# Sensors_v2.net
KiCad netlist of a schematic drawn in EAGLE
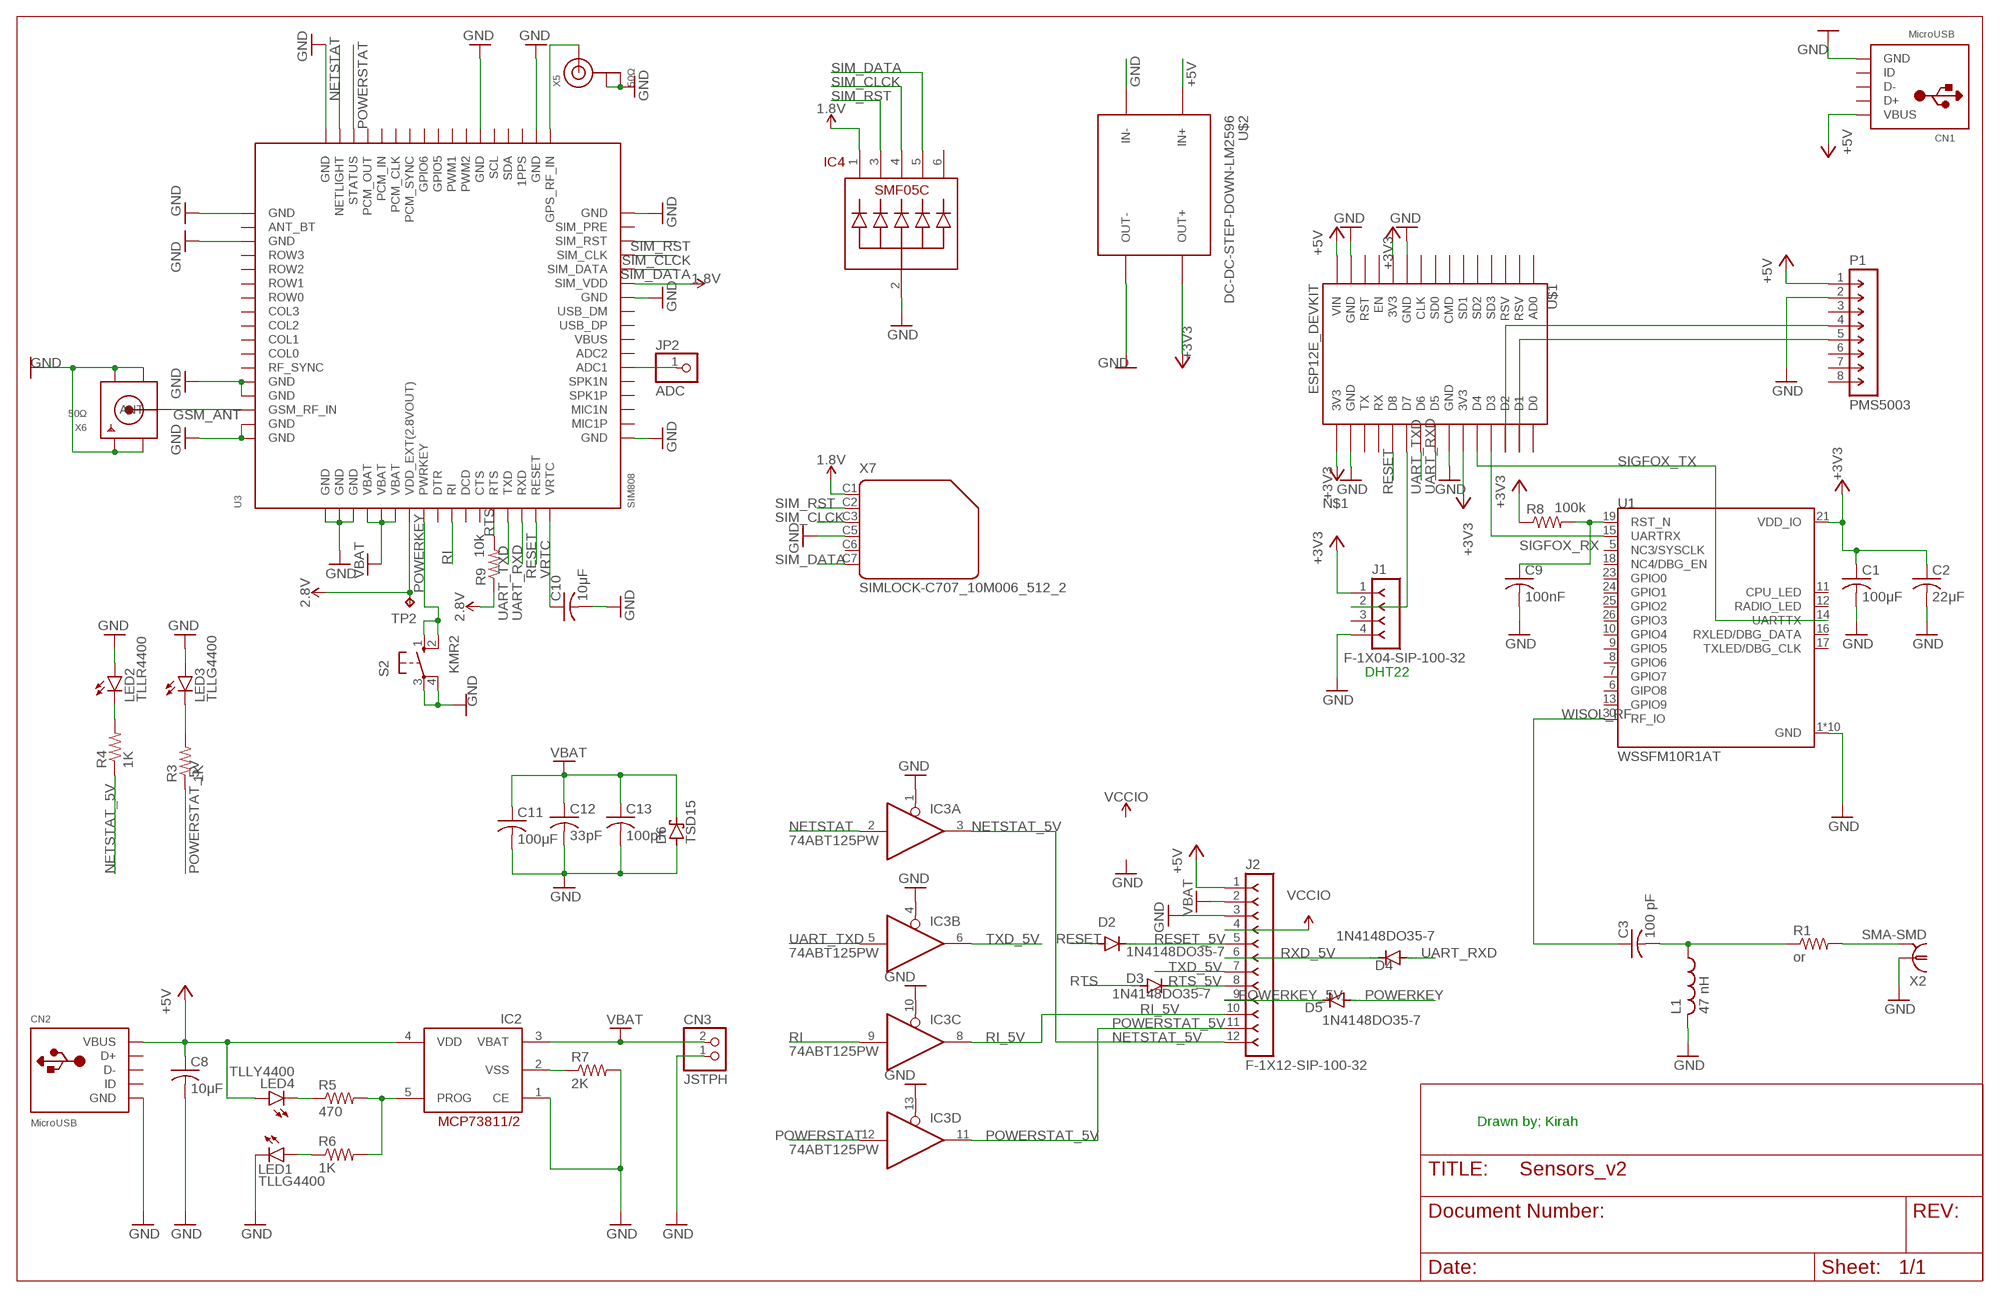
[diagram p0: schematic, sheet 1]

(export (version "E")
  (design (tool "Eeschema 10.0.6"))
  (components
    (comp (ref "C1")
      (value "100μF")
      (footprint "eagle-import:C0201")
      (libsource (lib "eagle-import") (part "C-USC0201"))
    )
    (comp (ref "C2")
      (value "22μF")
      (footprint "eagle-import:C0201")
      (libsource (lib "eagle-import") (part "C-USC0201"))
    )
    (comp (ref "C3")
      (value "100 pF")
      (footprint "eagle-import:C0201")
      (libsource (lib "eagle-import") (part "C-USC0201"))
    )
    (comp (ref "C8")
      (value "10μF")
      (footprint "eagle-import:C025-025X050")
      (libsource (lib "eagle-import") (part "C-US025-025X050"))
    )
    (comp (ref "C9")
      (value "100nF")
      (footprint "eagle-import:C025-025X050")
      (libsource (lib "eagle-import") (part "rcl_C-US025-025X050"))
    )
    (comp (ref "C10")
      (value "10μF")
      (footprint "eagle-import:C0402")
      (libsource (lib "eagle-import") (part "rcl_C-USC0402"))
    )
    (comp (ref "C11")
      (value "100μF")
      (footprint "eagle-import:C0402")
      (libsource (lib "eagle-import") (part "rcl_C-USC0402"))
    )
    (comp (ref "C12")
      (value "33pF")
      (footprint "eagle-import:C0402")
      (libsource (lib "eagle-import") (part "rcl_C-USC0402"))
    )
    (comp (ref "C13")
      (value "100pF")
      (footprint "eagle-import:C0402")
      (libsource (lib "eagle-import") (part "rcl_C-USC0402"))
    )
    (comp (ref "CN1")
      (value "MicroUSB")
      (footprint "eagle-import:USB-MINIB")
      (libsource (lib "eagle-import") (part "USBMINIB"))
    )
    (comp (ref "CN2")
      (value "MicroUSB")
      (footprint "eagle-import:USB-MINIB")
      (libsource (lib "eagle-import") (part "adafruit@1_USBMINIB"))
    )
    (comp (ref "CN3")
      (value "JSTPH")
      (footprint "eagle-import:JST-PH-2-SMT")
      (libsource (lib "eagle-import") (part "JST_2PIN-SMT"))
    )
    (comp (ref "D2")
      (value "1N4148DO35-7")
      (footprint "eagle-import:DO35-7")
      (libsource (lib "eagle-import") (part "1N4148DO35-7"))
    )
    (comp (ref "D3")
      (value "1N4148DO35-7")
      (footprint "eagle-import:DO35-7")
      (libsource (lib "eagle-import") (part "1N4148DO35-7"))
    )
    (comp (ref "D4")
      (value "1N4148DO35-7")
      (footprint "eagle-import:DO35-7")
      (libsource (lib "eagle-import") (part "1N4148DO35-7"))
    )
    (comp (ref "D5")
      (value "1N4148DO35-7")
      (footprint "eagle-import:DO35-7")
      (libsource (lib "eagle-import") (part "1N4148DO35-7"))
    )
    (comp (ref "D6")
      (value "TSD15")
      (footprint "eagle-import:CB429-15")
      (libsource (lib "eagle-import") (part "TSD15"))
    )
    (comp (ref "IC2")
      (value "MCP73811/2")
      (footprint "eagle-import:SOT23-5L")
      (libsource (lib "eagle-import") (part "MCP73811/2"))
    )
    (comp (ref "IC3")
      (value "74ABT125PW")
      (footprint "eagle-import:TSSOP14")
      (libsource (lib "eagle-import") (part "74125PWABT"))
    )
    (comp (ref "IC4")
      (value "SMF05C")
      (footprint "eagle-import:SC-70-6")
      (libsource (lib "eagle-import") (part "SMF05C"))
    )
    (comp (ref "J1")
      (value "F-1X04-SIP-100-32")
      (footprint "eagle-import:SIP-100-04-32")
      (libsource (lib "eagle-import") (part "F-1X04-SIP-100-32"))
    )
    (comp (ref "J2")
      (value "F-1X12-SIP-100-32")
      (footprint "eagle-import:SIP-100-12-32")
      (libsource (lib "eagle-import") (part "F-1X12-SIP-100-32"))
    )
    (comp (ref "JP2")
      (value "ADC")
      (footprint "eagle-import:1X01M")
      (libsource (lib "eagle-import") (part "PINHD-1X01_2.00"))
    )
    (comp (ref "L1")
      (value "47 nH")
      (footprint "eagle-import:0204_7")
      (libsource (lib "eagle-import") (part "L-US0204/7"))
    )
    (comp (ref "LED1")
      (value "TLLG4400")
      (footprint "eagle-import:LED3MM")
      (fields (field (name "MF") "VISHAY SEMICONDUCTOR"))
      (libsource (lib "eagle-import") (part "TLLG4400"))
    )
    (comp (ref "LED2")
      (value "TLLR4400")
      (footprint "eagle-import:LED3MM")
      (fields (field (name "MF") "VISHAY SEMICONDUCTOR"))
      (libsource (lib "eagle-import") (part "TLLR4400"))
    )
    (comp (ref "LED3")
      (value "TLLG4400")
      (footprint "eagle-import:LED3MM")
      (fields (field (name "MF") "VISHAY SEMICONDUCTOR"))
      (libsource (lib "eagle-import") (part "TLLG4400"))
    )
    (comp (ref "LED4")
      (value "TLLY4400")
      (footprint "eagle-import:LED3MM")
      (fields (field (name "MF") "VISHAY SEMICONDUCTOR"))
      (libsource (lib "eagle-import") (part "TLLY4400"))
    )
    (comp (ref "P1")
      (value "PMS5003")
      (footprint "eagle-import:SIP-100-08-40")
      (libsource (lib "eagle-import") (part "M-1X08-SIP-100-40"))
    )
    (comp (ref "R1")
      (value "or")
      (footprint "eagle-import:0204_5")
      (libsource (lib "eagle-import") (part "R-US_0204/5"))
    )
    (comp (ref "R3")
      (value "1K")
      (footprint "eagle-import:0204_5")
      (libsource (lib "eagle-import") (part "R-US_0204/5"))
    )
    (comp (ref "R4")
      (value "1K")
      (footprint "eagle-import:0204_5")
      (libsource (lib "eagle-import") (part "R-US_0204/5"))
    )
    (comp (ref "R5")
      (value "470")
      (footprint "eagle-import:0204_5")
      (libsource (lib "eagle-import") (part "R-US_0204/5"))
    )
    (comp (ref "R6")
      (value "1K")
      (footprint "eagle-import:0204_5")
      (libsource (lib "eagle-import") (part "R-US_0204/5"))
    )
    (comp (ref "R7")
      (value "2K")
      (footprint "eagle-import:0204_5")
      (libsource (lib "eagle-import") (part "R-US_0204/5"))
    )
    (comp (ref "R8")
      (value "100k")
      (footprint "eagle-import:0204_7")
      (libsource (lib "eagle-import") (part "R-US_0204/7"))
    )
    (comp (ref "R9")
      (value "10k")
      (footprint "eagle-import:0204_5")
      (libsource (lib "eagle-import") (part "R-US_0204/5"))
    )
    (comp (ref "S2")
      (value "KMR2")
      (footprint "eagle-import:B3F_40XX")
      (libsource (lib "eagle-import") (part "40/XX"))
    )
    (comp (ref "TP2")
      (value "TPTP10R")
      (footprint "eagle-import:TP10R")
      (libsource (lib "eagle-import") (part "TPTP10R"))
    )
    (comp (ref "U$1")
      (value "ESP12E_DEVKIT")
      (footprint "eagle-import:ESP12E_DEVKIT")
      (libsource (lib "eagle-import") (part "ESP12E_DEVKIT"))
    )
    (comp (ref "U$2")
      (value "DC-DC-STEP-DOWN-LM2596")
      (footprint "eagle-import:DC-DC-STEP-DOWN-LM2596")
      (libsource (lib "eagle-import") (part "DC-DC-STEP-DOWN-LM2596"))
    )
    (comp (ref "U1")
      (value "WSSFM10R1AT")
      (footprint "eagle-import:XCVR_WSSFM10R1AT")
      (fields (field (name "MF") "Avnet Design Services"))
      (libsource (lib "eagle-import") (part "WSSFM10R1AT"))
    )
    (comp (ref "U3")
      (value "SIM808")
      (footprint "eagle-import:SIM900_SMT")
      (libsource (lib "eagle-import") (part "GSM_SIM808_LITERAL"))
    )
    (comp (ref "X2")
      (value "SMA-SMD")
      (footprint "eagle-import:SMA-SMD")
      (libsource (lib "eagle-import") (part "SMA-SMD"))
    )
    (comp (ref "X5")
      (value "50Ω")
      (footprint "eagle-import:U.FL")
      (libsource (lib "eagle-import") (part "ANTENNA_U.FL"))
    )
    (comp (ref "X6")
      (value "50Ω")
      (footprint "eagle-import:SMA_EDGELAUNCH_UFL")
      (libsource (lib "eagle-import") (part "SMACONNECTOR_EDGE_UFL"))
    )
    (comp (ref "X7")
      (value "SIMLOCK-C707_10M006_512_2")
      (footprint "eagle-import:C707_10M006_512_2")
      (libsource (lib "eagle-import") (part "SIMLOCK-C707_10M006_512_2"))
    )
  )
  (nets
    (net (code "1") (name "+3V3") (class "Default")
      (node (ref "C1") (pin "1") (pinfunction "1_1") (pintype "passive"))
      (node (ref "C2") (pin "1") (pinfunction "1_1") (pintype "passive"))
      (node (ref "J1") (pin "1") (pinfunction "1_1") (pintype "passive"))
      (node (ref "R8") (pin "1") (pinfunction "1_1") (pintype "passive"))
      (node (ref "U$1") (pin "3V3@0") (pinfunction "3V3_3V3@0") (pintype "bidirectional"))
      (node (ref "U$1") (pin "3V3@1") (pinfunction "3V3_3V3@1") (pintype "bidirectional"))
      (node (ref "U$1") (pin "3V3@2") (pinfunction "3V3_3V3@2") (pintype "bidirectional"))
      (node (ref "U$2") (pin "OUT+") (pinfunction "OUT+_OUT+") (pintype "bidirectional"))
      (node (ref "U1") (pin "21") (pinfunction "VDD_IO_21") (pintype "power_in"))
    )
    (net (code "2") (name "+5V") (class "Default")
      (node (ref "C8") (pin "1") (pinfunction "1_1") (pintype "passive"))
      (node (ref "CN1") (pin "VBUS") (pinfunction "VBUS_VBUS") (pintype "power_in"))
      (node (ref "CN2") (pin "VBUS") (pinfunction "VBUS_VBUS") (pintype "power_in"))
      (node (ref "IC2") (pin "4") (pinfunction "VDD_4") (pintype "power_in"))
      (node (ref "J2") (pin "1") (pinfunction "1_1") (pintype "passive"))
      (node (ref "LED4") (pin "A") (pinfunction "A_A") (pintype "passive"))
      (node (ref "P1") (pin "1") (pinfunction "1_1") (pintype "passive"))
      (node (ref "U$1") (pin "VIN") (pinfunction "VIN_VIN") (pintype "bidirectional"))
      (node (ref "U$2") (pin "IN+") (pinfunction "IN+_IN+") (pintype "bidirectional"))
    )
    (net (code "3") (name "/GSM_ANT") (class "Default")
      (node (ref "U3") (pin "P$66") (pinfunction "GSM_RF_IN_P$66") (pintype "input"))
      (node (ref "X6") (pin "P") (pinfunction "ANT_P") (pintype "bidirectional"))
    )
    (net (code "4") (name "/N$1") (class "Default")
      (node (ref "J1") (pin "2") (pinfunction "2_2") (pintype "passive"))
      (node (ref "U$1") (pin "D7") (pinfunction "D7_D7") (pintype "bidirectional"))
    )
    (net (code "5") (name "/NETSTAT") (class "Default")
      (node (ref "IC3") (pin "2") (pinfunction "I_2") (pintype "input"))
      (node (ref "U3") (pin "P$50") (pinfunction "NETLIGHT_P$50") (pintype "output"))
    )
    (net (code "6") (name "/NETSTAT_5V") (class "Default")
      (node (ref "IC3") (pin "3") (pinfunction "O_3") (pintype "tri_state"))
      (node (ref "J2") (pin "12") (pinfunction "12_12") (pintype "passive"))
      (node (ref "R4") (pin "1") (pinfunction "1_1") (pintype "passive"))
    )
    (net (code "7") (name "/POWERKEY") (class "Default")
      (node (ref "D5") (pin "A") (pinfunction "A_A") (pintype "passive"))
      (node (ref "S2") (pin "1") (pinfunction "S_1") (pintype "passive"))
      (node (ref "S2") (pin "2") (pinfunction "S1_2") (pintype "passive"))
      (node (ref "U3") (pin "P$8") (pinfunction "PWRKEY_P$8") (pintype "input"))
    )
    (net (code "8") (name "/POWERKEY_5V") (class "Default")
      (node (ref "D5") (pin "C") (pinfunction "C_C") (pintype "passive"))
      (node (ref "J2") (pin "9") (pinfunction "9_9") (pintype "passive"))
    )
    (net (code "9") (name "/POWERSTAT") (class "Default")
      (node (ref "IC3") (pin "12") (pinfunction "I_12") (pintype "input"))
      (node (ref "U3") (pin "P$49") (pinfunction "STATUS_P$49") (pintype "output"))
    )
    (net (code "10") (name "/POWERSTAT_5V") (class "Default")
      (node (ref "IC3") (pin "11") (pinfunction "O_11") (pintype "tri_state"))
      (node (ref "J2") (pin "11") (pinfunction "11_11") (pintype "passive"))
      (node (ref "R3") (pin "1") (pinfunction "1_1") (pintype "passive"))
    )
    (net (code "11") (name "/RESET") (class "Default")
      (node (ref "D2") (pin "A") (pinfunction "A_A") (pintype "passive"))
      (node (ref "U$1") (pin "D8") (pinfunction "D8_D8") (pintype "bidirectional"))
      (node (ref "U3") (pin "P$16") (pinfunction "RESET_P$16") (pintype "input"))
    )
    (net (code "12") (name "/RESET_5V") (class "Default")
      (node (ref "D2") (pin "C") (pinfunction "C_C") (pintype "passive"))
      (node (ref "J2") (pin "5") (pinfunction "5_5") (pintype "passive"))
    )
    (net (code "13") (name "/RI") (class "Default")
      (node (ref "IC3") (pin "9") (pinfunction "I_9") (pintype "input"))
      (node (ref "U3") (pin "P$10") (pinfunction "RI_P$10") (pintype "output"))
    )
    (net (code "14") (name "/RI_5V") (class "Default")
      (node (ref "IC3") (pin "8") (pinfunction "O_8") (pintype "tri_state"))
      (node (ref "J2") (pin "10") (pinfunction "10_10") (pintype "passive"))
    )
    (net (code "15") (name "/RTS") (class "Default")
      (node (ref "D3") (pin "A") (pinfunction "A_A") (pintype "passive"))
      (node (ref "R9") (pin "2") (pinfunction "2_2") (pintype "passive"))
      (node (ref "U3") (pin "P$13") (pinfunction "RTS_P$13") (pintype "input"))
    )
    (net (code "16") (name "/RTS_5V") (class "Default")
      (node (ref "D3") (pin "C") (pinfunction "C_C") (pintype "passive"))
      (node (ref "J2") (pin "8") (pinfunction "8_8") (pintype "passive"))
    )
    (net (code "17") (name "/RXD_5V") (class "Default")
      (node (ref "D4") (pin "C") (pinfunction "C_C") (pintype "passive"))
      (node (ref "J2") (pin "6") (pinfunction "6_6") (pintype "passive"))
    )
    (net (code "18") (name "/SIGFOX_RX") (class "Default")
      (node (ref "U$1") (pin "D3") (pinfunction "D3_D3") (pintype "bidirectional"))
      (node (ref "U1") (pin "15") (pinfunction "UARTRX_15") (pintype "input"))
    )
    (net (code "19") (name "/SIGFOX_TX") (class "Default")
      (node (ref "U$1") (pin "D4") (pinfunction "D4_D4") (pintype "bidirectional"))
      (node (ref "U1") (pin "14") (pinfunction "UARTTX_14") (pintype "output"))
    )
    (net (code "20") (name "/SIM_CLCK") (class "Default")
      (node (ref "IC4") (pin "4") (pinfunction "4_4") (pintype "bidirectional"))
      (node (ref "U3") (pin "P$31") (pinfunction "SIM_CLK_P$31") (pintype "output"))
      (node (ref "X7") (pin "C3") (pinfunction "3_C3") (pintype "passive"))
    )
    (net (code "21") (name "/SIM_DATA") (class "Default")
      (node (ref "IC4") (pin "5") (pinfunction "5_5") (pintype "bidirectional"))
      (node (ref "U3") (pin "P$30") (pinfunction "SIM_DATA_P$30") (pintype "bidirectional"))
      (node (ref "X7") (pin "C7") (pinfunction "6_C7") (pintype "passive"))
    )
    (net (code "22") (name "/SIM_RST") (class "Default")
      (node (ref "IC4") (pin "3") (pinfunction "3_3") (pintype "bidirectional"))
      (node (ref "U3") (pin "P$32") (pinfunction "SIM_RST_P$32") (pintype "output"))
      (node (ref "X7") (pin "C2") (pinfunction "2_C2") (pintype "passive"))
    )
    (net (code "23") (name "/TXD_5V") (class "Default")
      (node (ref "IC3") (pin "6") (pinfunction "O_6") (pintype "tri_state"))
      (node (ref "J2") (pin "7") (pinfunction "7_7") (pintype "passive"))
    )
    (net (code "24") (name "/UART_RXD") (class "Default")
      (node (ref "D4") (pin "A") (pinfunction "A_A") (pintype "passive"))
      (node (ref "U$1") (pin "D5") (pinfunction "D5_D5") (pintype "bidirectional"))
      (node (ref "U3") (pin "P$15") (pinfunction "RXD_P$15") (pintype "input"))
    )
    (net (code "25") (name "/UART_TXD") (class "Default")
      (node (ref "IC3") (pin "5") (pinfunction "I_5") (pintype "input"))
      (node (ref "U$1") (pin "D6") (pinfunction "D6_D6") (pintype "bidirectional"))
      (node (ref "U3") (pin "P$14") (pinfunction "TXD_P$14") (pintype "output"))
    )
    (net (code "26") (name "/VBUS") (class "Default")
      (node (ref "U3") (pin "P$25") (pinfunction "VBUS_P$25") (pintype "power_in"))
    )
    (net (code "27") (name "/VRTC") (class "Default")
      (node (ref "C10") (pin "1") (pinfunction "1_1") (pintype "passive"))
      (node (ref "U3") (pin "P$17") (pinfunction "VRTC_P$17") (pintype "power_in"))
    )
    (net (code "28") (name "/WISOL_RF") (class "Default")
      (node (ref "C3") (pin "1") (pinfunction "1_1") (pintype "passive"))
      (node (ref "U1") (pin "30") (pinfunction "RF_IO_30") (pintype "bidirectional"))
    )
    (net (code "29") (name "1.8V") (class "Default")
      (node (ref "IC4") (pin "1") (pinfunction "1_1") (pintype "bidirectional"))
      (node (ref "U3") (pin "P$29") (pinfunction "SIM_VDD_P$29") (pintype "power_in"))
      (node (ref "X7") (pin "C1") (pinfunction "1_C1") (pintype "passive"))
    )
    (net (code "30") (name "2.8V") (class "Default")
      (node (ref "R9") (pin "1") (pinfunction "1_1") (pintype "passive"))
      (node (ref "TP2") (pin "TP") (pinfunction "TP_TP") (pintype "input"))
      (node (ref "U3") (pin "P$7") (pinfunction "VDD_EXT(2.8VOUT)_P$7") (pintype "power_in"))
    )
    (net (code "31") (name "GND") (class "Default")
      (node (ref "C1") (pin "2") (pinfunction "2_2") (pintype "passive"))
      (node (ref "C10") (pin "2") (pinfunction "2_2") (pintype "passive"))
      (node (ref "C11") (pin "2") (pinfunction "2_2") (pintype "passive"))
      (node (ref "C12") (pin "2") (pinfunction "2_2") (pintype "passive"))
      (node (ref "C13") (pin "2") (pinfunction "2_2") (pintype "passive"))
      (node (ref "C2") (pin "2") (pinfunction "2_2") (pintype "passive"))
      (node (ref "C8") (pin "2") (pinfunction "2_2") (pintype "passive"))
      (node (ref "C9") (pin "2") (pinfunction "2_2") (pintype "passive"))
      (node (ref "CN1") (pin "GND") (pinfunction "GND_GND") (pintype "power_in"))
      (node (ref "CN2") (pin "GND") (pinfunction "GND_GND") (pintype "power_in"))
      (node (ref "CN3") (pin "1") (pinfunction "2_1") (pintype "passive"))
      (node (ref "D6") (pin "A") (pinfunction "A_A") (pintype "passive"))
      (node (ref "IC2") (pin "1") (pinfunction "CE_1") (pintype "input"))
      (node (ref "IC3") (pin "1") (pinfunction "OE_1") (pintype "input"))
      (node (ref "IC3") (pin "10") (pinfunction "OE_10") (pintype "input"))
      (node (ref "IC3") (pin "13") (pinfunction "OE_13") (pintype "input"))
      (node (ref "IC3") (pin "4") (pinfunction "OE_4") (pintype "input"))
      (node (ref "IC4") (pin "2") (pinfunction "2_2") (pintype "bidirectional"))
      (node (ref "J1") (pin "4") (pinfunction "4_4") (pintype "passive"))
      (node (ref "J2") (pin "3") (pinfunction "3_3") (pintype "passive"))
      (node (ref "L1") (pin "2") (pinfunction "2_2") (pintype "passive"))
      (node (ref "LED1") (pin "K") (pinfunction "C_K") (pintype "passive"))
      (node (ref "LED2") (pin "A") (pinfunction "A_A") (pintype "passive"))
      (node (ref "LED3") (pin "A") (pinfunction "A_A") (pintype "passive"))
      (node (ref "P1") (pin "2") (pinfunction "2_2") (pintype "passive"))
      (node (ref "R7") (pin "2") (pinfunction "2_2") (pintype "passive"))
      (node (ref "S2") (pin "3") (pinfunction "P_3") (pintype "passive"))
      (node (ref "S2") (pin "4") (pinfunction "P1_4") (pintype "passive"))
      (node (ref "U$1") (pin "GND@0") (pinfunction "GND_GND@0") (pintype "bidirectional"))
      (node (ref "U$1") (pin "GND@1") (pinfunction "GND_GND@1") (pintype "bidirectional"))
      (node (ref "U$1") (pin "GND@2") (pinfunction "GND_GND@2") (pintype "bidirectional"))
      (node (ref "U$1") (pin "GND@3") (pinfunction "GND_GND@3") (pintype "bidirectional"))
      (node (ref "U$2") (pin "IN-") (pinfunction "IN-_IN-") (pintype "bidirectional"))
      (node (ref "U$2") (pin "OUT-") (pinfunction "OUT-_OUT-") (pintype "bidirectional"))
      (node (ref "U1") (pin "1") (pinfunction "GND_1") (pintype "power_in"))
      (node (ref "U1") (pin "2") (pinfunction "GND_2") (pintype "power_in"))
      (node (ref "U1") (pin "20") (pinfunction "GND_20") (pintype "power_in"))
      (node (ref "U1") (pin "22") (pinfunction "GND_22") (pintype "power_in"))
      (node (ref "U1") (pin "27") (pinfunction "GND_27") (pintype "power_in"))
      (node (ref "U1") (pin "28") (pinfunction "GND_28") (pintype "power_in"))
      (node (ref "U1") (pin "29") (pinfunction "GND_29") (pintype "power_in"))
      (node (ref "U1") (pin "3") (pinfunction "GND_3") (pintype "power_in"))
      (node (ref "U1") (pin "31") (pinfunction "GND_31") (pintype "power_in"))
      (node (ref "U1") (pin "4") (pinfunction "GND_4") (pintype "power_in"))
      (node (ref "U3") (pin "P$1") (pinfunction "GND_P$1") (pintype "power_in"))
      (node (ref "U3") (pin "P$18") (pinfunction "GND_P$18") (pintype "power_in"))
      (node (ref "U3") (pin "P$2") (pinfunction "GND_P$2") (pintype "power_in"))
      (node (ref "U3") (pin "P$28") (pinfunction "GND_P$28") (pintype "power_in"))
      (node (ref "U3") (pin "P$3") (pinfunction "GND_P$3") (pintype "power_in"))
      (node (ref "U3") (pin "P$34") (pinfunction "GND_P$34") (pintype "power_in"))
      (node (ref "U3") (pin "P$36") (pinfunction "GND_P$36") (pintype "power_in"))
      (node (ref "U3") (pin "P$40") (pinfunction "GND_P$40") (pintype "power_in"))
      (node (ref "U3") (pin "P$51") (pinfunction "GND_P$51") (pintype "power_in"))
      (node (ref "U3") (pin "P$52") (pinfunction "GND_P$52") (pintype "power_in"))
      (node (ref "U3") (pin "P$54") (pinfunction "GND_P$54") (pintype "power_in"))
      (node (ref "U3") (pin "P$64") (pinfunction "GND_P$64") (pintype "power_in"))
      (node (ref "U3") (pin "P$65") (pinfunction "GND_P$65") (pintype "power_in"))
      (node (ref "U3") (pin "P$67") (pinfunction "GND_P$67") (pintype "power_in"))
      (node (ref "U3") (pin "P$68") (pinfunction "GND_P$68") (pintype "power_in"))
      (node (ref "X2") (pin "1") (pinfunction "1_1") (pintype "passive"))
      (node (ref "X5") (pin "1") (pinfunction "GND_1") (pintype "passive"))
      (node (ref "X5") (pin "2") (pinfunction "GND_2") (pintype "passive"))
      (node (ref "X6") (pin "GND@1") (pinfunction "GND1_GND@1") (pintype "power_in"))
      (node (ref "X6") (pin "GND@2") (pinfunction "GND2_GND@2") (pintype "power_in"))
      (node (ref "X6") (pin "GND@3") (pinfunction "GND3_GND@3") (pintype "power_in"))
      (node (ref "X6") (pin "GND@4") (pinfunction "GND4_GND@4") (pintype "power_in"))
      (node (ref "X7") (pin "C5") (pinfunction "4_C5") (pintype "passive"))
    )
    (net (code "32") (name "Net-(C3-Pad2)") (class "Default")
      (node (ref "C3") (pin "2") (pinfunction "2_2") (pintype "passive"))
      (node (ref "L1") (pin "1") (pinfunction "1_1") (pintype "passive"))
      (node (ref "R1") (pin "1") (pinfunction "1_1") (pintype "passive"))
    )
    (net (code "33") (name "Net-(IC2-PROG)") (class "Default")
      (node (ref "IC2") (pin "5") (pinfunction "PROG_5") (pintype "input"))
      (node (ref "R5") (pin "2") (pinfunction "2_2") (pintype "passive"))
      (node (ref "R6") (pin "2") (pinfunction "2_2") (pintype "passive"))
    )
    (net (code "34") (name "Net-(IC2-VSS)") (class "Default")
      (node (ref "IC2") (pin "2") (pinfunction "VSS_2") (pintype "power_in"))
      (node (ref "R7") (pin "1") (pinfunction "1_1") (pintype "passive"))
    )
    (net (code "35") (name "Net-(LED1-PadA)") (class "Default")
      (node (ref "LED1") (pin "A") (pinfunction "A_A") (pintype "passive"))
      (node (ref "R6") (pin "1") (pinfunction "1_1") (pintype "passive"))
    )
    (net (code "36") (name "Net-(LED2-C)") (class "Default")
      (node (ref "LED2") (pin "K") (pinfunction "C_K") (pintype "passive"))
      (node (ref "R4") (pin "2") (pinfunction "2_2") (pintype "passive"))
    )
    (net (code "37") (name "Net-(LED3-C)") (class "Default")
      (node (ref "LED3") (pin "K") (pinfunction "C_K") (pintype "passive"))
      (node (ref "R3") (pin "2") (pinfunction "2_2") (pintype "passive"))
    )
    (net (code "38") (name "Net-(LED4-C)") (class "Default")
      (node (ref "LED4") (pin "K") (pinfunction "C_K") (pintype "passive"))
      (node (ref "R5") (pin "1") (pinfunction "1_1") (pintype "passive"))
    )
    (net (code "39") (name "Net-(P1-Pad4)") (class "Default")
      (node (ref "P1") (pin "4") (pinfunction "4_4") (pintype "passive"))
      (node (ref "U$1") (pin "D2") (pinfunction "D2_D2") (pintype "bidirectional"))
    )
    (net (code "40") (name "Net-(P1-Pad5)") (class "Default")
      (node (ref "P1") (pin "5") (pinfunction "5_5") (pintype "passive"))
      (node (ref "U$1") (pin "D1") (pinfunction "D1_D1") (pintype "bidirectional"))
    )
    (net (code "41") (name "Net-(R1-Pad2)") (class "Default")
      (node (ref "R1") (pin "2") (pinfunction "2_2") (pintype "passive"))
      (node (ref "X2") (pin "2@1") (pinfunction "2_2@1") (pintype "passive"))
      (node (ref "X2") (pin "2@2") (pinfunction "2_2@2") (pintype "passive"))
      (node (ref "X2") (pin "2@3") (pinfunction "2_2@3") (pintype "passive"))
      (node (ref "X2") (pin "2@4") (pinfunction "2_2@4") (pintype "passive"))
      (node (ref "X2") (pin "2@5") (pinfunction "2_2@5") (pintype "passive"))
      (node (ref "X2") (pin "2@6") (pinfunction "2_2@6") (pintype "passive"))
    )
    (net (code "42") (name "Net-(U1-RST_N)") (class "Default")
      (node (ref "C9") (pin "1") (pinfunction "1_1") (pintype "passive"))
      (node (ref "R8") (pin "2") (pinfunction "2_2") (pintype "passive"))
      (node (ref "U1") (pin "19") (pinfunction "RST_N_19") (pintype "input"))
    )
    (net (code "43") (name "Net-(U3-ADC1)") (class "Default")
      (node (ref "JP2") (pin "1") (pinfunction "1_1") (pintype "passive"))
      (node (ref "U3") (pin "P$23") (pinfunction "ADC1_P$23") (pintype "input"))
    )
    (net (code "44") (name "Net-(U3-GPS_RF_IN)") (class "Default")
      (node (ref "U3") (pin "P$35") (pinfunction "GPS_RF_IN_P$35") (pintype "bidirectional"))
      (node (ref "X5") (pin "3") (pinfunction "SIGNAL_3") (pintype "passive"))
    )
    (net (code "45") (name "VBAT") (class "Default")
      (node (ref "C11") (pin "1") (pinfunction "1_1") (pintype "passive"))
      (node (ref "C12") (pin "1") (pinfunction "1_1") (pintype "passive"))
      (node (ref "C13") (pin "1") (pinfunction "1_1") (pintype "passive"))
      (node (ref "CN3") (pin "2") (pinfunction "1_2") (pintype "passive"))
      (node (ref "D6") (pin "C") (pinfunction "C_C") (pintype "passive"))
      (node (ref "IC2") (pin "3") (pinfunction "VBAT_3") (pintype "bidirectional"))
      (node (ref "J2") (pin "2") (pinfunction "2_2") (pintype "passive"))
      (node (ref "U3") (pin "P$4") (pinfunction "VBAT_P$4") (pintype "power_in"))
      (node (ref "U3") (pin "P$5") (pinfunction "VBAT_P$5") (pintype "power_in"))
      (node (ref "U3") (pin "P$6") (pinfunction "VBAT_P$6") (pintype "power_in"))
    )
    (net (code "46") (name "VCCIO") (class "Default")
      (node (ref "J2") (pin "4") (pinfunction "4_4") (pintype "passive"))
    )
    (net (code "47") (name "unconnected-(CN1-PadD+)") (class "Default")
      (node (ref "CN1") (pin "D+") (pinfunction "D+_D+") (pintype "bidirectional"))
    )
    (net (code "48") (name "unconnected-(CN1-PadD-)") (class "Default")
      (node (ref "CN1") (pin "D-") (pinfunction "D-_D-") (pintype "bidirectional"))
    )
    (net (code "49") (name "unconnected-(CN1-PadID)") (class "Default")
      (node (ref "CN1") (pin "ID") (pinfunction "ID_ID") (pintype "bidirectional"))
    )
    (net (code "50") (name "unconnected-(CN2-PadD+)") (class "Default")
      (node (ref "CN2") (pin "D+") (pinfunction "D+_D+") (pintype "bidirectional"))
    )
    (net (code "51") (name "unconnected-(CN2-PadD-)") (class "Default")
      (node (ref "CN2") (pin "D-") (pinfunction "D-_D-") (pintype "bidirectional"))
    )
    (net (code "52") (name "unconnected-(CN2-PadID)") (class "Default")
      (node (ref "CN2") (pin "ID") (pinfunction "ID_ID") (pintype "bidirectional"))
    )
    (net (code "53") (name "unconnected-(IC4-Pad6)") (class "Default")
      (node (ref "IC4") (pin "6") (pinfunction "6_6") (pintype "bidirectional"))
    )
    (net (code "54") (name "unconnected-(J1-Pad3)") (class "Default")
      (node (ref "J1") (pin "3") (pinfunction "3_3") (pintype "passive"))
    )
    (net (code "55") (name "unconnected-(P1-Pad3)") (class "Default")
      (node (ref "P1") (pin "3") (pinfunction "3_3") (pintype "passive"))
    )
    (net (code "56") (name "unconnected-(P1-Pad6)") (class "Default")
      (node (ref "P1") (pin "6") (pinfunction "6_6") (pintype "passive"))
    )
    (net (code "57") (name "unconnected-(P1-Pad7)") (class "Default")
      (node (ref "P1") (pin "7") (pinfunction "7_7") (pintype "passive"))
    )
    (net (code "58") (name "unconnected-(P1-Pad8)") (class "Default")
      (node (ref "P1") (pin "8") (pinfunction "8_8") (pintype "passive"))
    )
    (net (code "59") (name "unconnected-(U$1-PadAD0)") (class "Default")
      (node (ref "U$1") (pin "AD0") (pinfunction "AD0_AD0") (pintype "bidirectional"))
    )
    (net (code "60") (name "unconnected-(U$1-PadCLK)") (class "Default")
      (node (ref "U$1") (pin "CLK") (pinfunction "CLK_CLK") (pintype "bidirectional"))
    )
    (net (code "61") (name "unconnected-(U$1-PadCMD)") (class "Default")
      (node (ref "U$1") (pin "CMD") (pinfunction "CMD_CMD") (pintype "bidirectional"))
    )
    (net (code "62") (name "unconnected-(U$1-PadD0)") (class "Default")
      (node (ref "U$1") (pin "D0") (pinfunction "D0_D0") (pintype "bidirectional"))
    )
    (net (code "63") (name "unconnected-(U$1-PadEN)") (class "Default")
      (node (ref "U$1") (pin "EN") (pinfunction "EN_EN") (pintype "bidirectional"))
    )
    (net (code "64") (name "unconnected-(U$1-PadRST)") (class "Default")
      (node (ref "U$1") (pin "RST") (pinfunction "RST_RST") (pintype "bidirectional"))
    )
    (net (code "65") (name "unconnected-(U$1-PadRX)") (class "Default")
      (node (ref "U$1") (pin "RX") (pinfunction "RX_RX") (pintype "bidirectional"))
    )
    (net (code "66") (name "unconnected-(U$1-PadSD0)") (class "Default")
      (node (ref "U$1") (pin "SD0") (pinfunction "SD0_SD0") (pintype "bidirectional"))
    )
    (net (code "67") (name "unconnected-(U$1-PadSD1)") (class "Default")
      (node (ref "U$1") (pin "SD1") (pinfunction "SD1_SD1") (pintype "bidirectional"))
    )
    (net (code "68") (name "unconnected-(U$1-PadSD2)") (class "Default")
      (node (ref "U$1") (pin "SD2") (pinfunction "SD2_SD2") (pintype "bidirectional"))
    )
    (net (code "69") (name "unconnected-(U$1-PadSD3)") (class "Default")
      (node (ref "U$1") (pin "SD3") (pinfunction "SD3_SD3") (pintype "bidirectional"))
    )
    (net (code "70") (name "unconnected-(U$1-PadTX)") (class "Default")
      (node (ref "U$1") (pin "TX") (pinfunction "TX_TX") (pintype "bidirectional"))
    )
    (net (code "71") (name "unconnected-(U$1-RSV-PadRSV@0)") (class "Default")
      (node (ref "U$1") (pin "RSV@0") (pinfunction "RSV_RSV@0") (pintype "bidirectional"))
    )
    (net (code "72") (name "unconnected-(U$1-RSV-PadRSV@1)") (class "Default")
      (node (ref "U$1") (pin "RSV@1") (pinfunction "RSV_RSV@1") (pintype "bidirectional"))
    )
    (net (code "73") (name "unconnected-(U1-CPU_LED-Pad11)") (class "Default")
      (node (ref "U1") (pin "11") (pinfunction "CPU_LED_11") (pintype "output"))
    )
    (net (code "74") (name "unconnected-(U1-GIPO8-Pad6)") (class "Default")
      (node (ref "U1") (pin "6") (pinfunction "GIPO8_6") (pintype "bidirectional"))
    )
    (net (code "75") (name "unconnected-(U1-GPIO0-Pad23)") (class "Default")
      (node (ref "U1") (pin "23") (pinfunction "GPIO0_23") (pintype "bidirectional"))
    )
    (net (code "76") (name "unconnected-(U1-GPIO1-Pad24)") (class "Default")
      (node (ref "U1") (pin "24") (pinfunction "GPIO1_24") (pintype "bidirectional"))
    )
    (net (code "77") (name "unconnected-(U1-GPIO2-Pad25)") (class "Default")
      (node (ref "U1") (pin "25") (pinfunction "GPIO2_25") (pintype "bidirectional"))
    )
    (net (code "78") (name "unconnected-(U1-GPIO3-Pad26)") (class "Default")
      (node (ref "U1") (pin "26") (pinfunction "GPIO3_26") (pintype "bidirectional"))
    )
    (net (code "79") (name "unconnected-(U1-GPIO4-Pad10)") (class "Default")
      (node (ref "U1") (pin "10") (pinfunction "GPIO4_10") (pintype "input"))
    )
    (net (code "80") (name "unconnected-(U1-GPIO5-Pad9)") (class "Default")
      (node (ref "U1") (pin "9") (pinfunction "GPIO5_9") (pintype "bidirectional"))
    )
    (net (code "81") (name "unconnected-(U1-GPIO6-Pad8)") (class "Default")
      (node (ref "U1") (pin "8") (pinfunction "GPIO6_8") (pintype "bidirectional"))
    )
    (net (code "82") (name "unconnected-(U1-GPIO7-Pad7)") (class "Default")
      (node (ref "U1") (pin "7") (pinfunction "GPIO7_7") (pintype "bidirectional"))
    )
    (net (code "83") (name "unconnected-(U1-GPIO9-Pad13)") (class "Default")
      (node (ref "U1") (pin "13") (pinfunction "GPIO9_13") (pintype "input"))
    )
    (net (code "84") (name "unconnected-(U1-NC3{slash}SYSCLK-Pad5)") (class "Default")
      (node (ref "U1") (pin "5") (pinfunction "NC3/SYSCLK_5") (pintype "input"))
    )
    (net (code "85") (name "unconnected-(U1-NC4{slash}DBG_EN-Pad18)") (class "Default")
      (node (ref "U1") (pin "18") (pinfunction "NC4/DBG_EN_18") (pintype "input"))
    )
    (net (code "86") (name "unconnected-(U1-RADIO_LED-Pad12)") (class "Default")
      (node (ref "U1") (pin "12") (pinfunction "RADIO_LED_12") (pintype "output"))
    )
    (net (code "87") (name "unconnected-(U1-RXLED{slash}DBG_DATA-Pad16)") (class "Default")
      (node (ref "U1") (pin "16") (pinfunction "RXLED/DBG_DATA_16") (pintype "output"))
    )
    (net (code "88") (name "unconnected-(U1-TXLED{slash}DBG_CLK-Pad17)") (class "Default")
      (node (ref "U1") (pin "17") (pinfunction "TXLED/DBG_CLK_17") (pintype "output"))
    )
    (net (code "89") (name "unconnected-(U3-1PPS-PadP$37)") (class "Default")
      (node (ref "U3") (pin "P$37") (pinfunction "1PPS_P$37") (pintype "input"))
    )
    (net (code "90") (name "unconnected-(U3-ADC2-PadP$24)") (class "Default")
      (node (ref "U3") (pin "P$24") (pinfunction "ADC2_P$24") (pintype "input"))
    )
    (net (code "91") (name "unconnected-(U3-ANT_BT-PadP$53)") (class "Default")
      (node (ref "U3") (pin "P$53") (pinfunction "ANT_BT_P$53") (pintype "bidirectional"))
    )
    (net (code "92") (name "unconnected-(U3-COL0-PadP$62)") (class "Default")
      (node (ref "U3") (pin "P$62") (pinfunction "COL0_P$62") (pintype "input"))
    )
    (net (code "93") (name "unconnected-(U3-COL1-PadP$61)") (class "Default")
      (node (ref "U3") (pin "P$61") (pinfunction "COL1_P$61") (pintype "input"))
    )
    (net (code "94") (name "unconnected-(U3-COL2-PadP$60)") (class "Default")
      (node (ref "U3") (pin "P$60") (pinfunction "COL2_P$60") (pintype "input"))
    )
    (net (code "95") (name "unconnected-(U3-COL3-PadP$59)") (class "Default")
      (node (ref "U3") (pin "P$59") (pinfunction "COL3_P$59") (pintype "input"))
    )
    (net (code "96") (name "unconnected-(U3-CTS-PadP$12)") (class "Default")
      (node (ref "U3") (pin "P$12") (pinfunction "CTS_P$12") (pintype "output"))
    )
    (net (code "97") (name "unconnected-(U3-DCD-PadP$11)") (class "Default")
      (node (ref "U3") (pin "P$11") (pinfunction "DCD_P$11") (pintype "output"))
    )
    (net (code "98") (name "unconnected-(U3-DTR-PadP$9)") (class "Default")
      (node (ref "U3") (pin "P$9") (pinfunction "DTR_P$9") (pintype "input"))
    )
    (net (code "99") (name "unconnected-(U3-GPIO5-PadP$43)") (class "Default")
      (node (ref "U3") (pin "P$43") (pinfunction "GPIO5_P$43") (pintype "bidirectional"))
    )
    (net (code "100") (name "unconnected-(U3-GPIO6-PadP$44)") (class "Default")
      (node (ref "U3") (pin "P$44") (pinfunction "GPIO6_P$44") (pintype "bidirectional"))
    )
    (net (code "101") (name "unconnected-(U3-MIC1N-PadP$20)") (class "Default")
      (node (ref "U3") (pin "P$20") (pinfunction "MIC1N_P$20") (pintype "input"))
    )
    (net (code "102") (name "unconnected-(U3-MIC1P-PadP$19)") (class "Default")
      (node (ref "U3") (pin "P$19") (pinfunction "MIC1P_P$19") (pintype "input"))
    )
    (net (code "103") (name "unconnected-(U3-PCM_CLK-PadP$46)") (class "Default")
      (node (ref "U3") (pin "P$46") (pinfunction "PCM_CLK_P$46") (pintype "input"))
    )
    (net (code "104") (name "unconnected-(U3-PCM_IN-PadP$47)") (class "Default")
      (node (ref "U3") (pin "P$47") (pinfunction "PCM_IN_P$47") (pintype "input"))
    )
    (net (code "105") (name "unconnected-(U3-PCM_OUT-PadP$48)") (class "Default")
      (node (ref "U3") (pin "P$48") (pinfunction "PCM_OUT_P$48") (pintype "output"))
    )
    (net (code "106") (name "unconnected-(U3-PCM_SYNC-PadP$45)") (class "Default")
      (node (ref "U3") (pin "P$45") (pinfunction "PCM_SYNC_P$45") (pintype "output"))
    )
    (net (code "107") (name "unconnected-(U3-PWM1-PadP$42)") (class "Default")
      (node (ref "U3") (pin "P$42") (pinfunction "PWM1_P$42") (pintype "output"))
    )
    (net (code "108") (name "unconnected-(U3-PWM2-PadP$41)") (class "Default")
      (node (ref "U3") (pin "P$41") (pinfunction "PWM2_P$41") (pintype "output"))
    )
    (net (code "109") (name "unconnected-(U3-RF_SYNC-PadP$63)") (class "Default")
      (node (ref "U3") (pin "P$63") (pinfunction "RF_SYNC_P$63") (pintype "output"))
    )
    (net (code "110") (name "unconnected-(U3-ROW0-PadP$58)") (class "Default")
      (node (ref "U3") (pin "P$58") (pinfunction "ROW0_P$58") (pintype "output"))
    )
    (net (code "111") (name "unconnected-(U3-ROW1-PadP$57)") (class "Default")
      (node (ref "U3") (pin "P$57") (pinfunction "ROW1_P$57") (pintype "output"))
    )
    (net (code "112") (name "unconnected-(U3-ROW2-PadP$56)") (class "Default")
      (node (ref "U3") (pin "P$56") (pinfunction "ROW2_P$56") (pintype "output"))
    )
    (net (code "113") (name "unconnected-(U3-ROW3-PadP$55)") (class "Default")
      (node (ref "U3") (pin "P$55") (pinfunction "ROW3_P$55") (pintype "output"))
    )
    (net (code "114") (name "unconnected-(U3-SCL-PadP$39)") (class "Default")
      (node (ref "U3") (pin "P$39") (pinfunction "SCL_P$39") (pintype "output"))
    )
    (net (code "115") (name "unconnected-(U3-SDA-PadP$38)") (class "Default")
      (node (ref "U3") (pin "P$38") (pinfunction "SDA_P$38") (pintype "bidirectional"))
    )
    (net (code "116") (name "unconnected-(U3-SIM_PRE-PadP$33)") (class "Default")
      (node (ref "U3") (pin "P$33") (pinfunction "SIM_PRE_P$33") (pintype "input"))
    )
    (net (code "117") (name "unconnected-(U3-SPK1N-PadP$22)") (class "Default")
      (node (ref "U3") (pin "P$22") (pinfunction "SPK1N_P$22") (pintype "output"))
    )
    (net (code "118") (name "unconnected-(U3-SPK1P-PadP$21)") (class "Default")
      (node (ref "U3") (pin "P$21") (pinfunction "SPK1P_P$21") (pintype "output"))
    )
    (net (code "119") (name "unconnected-(U3-USB_DM-PadP$27)") (class "Default")
      (node (ref "U3") (pin "P$27") (pinfunction "USB_DM_P$27") (pintype "bidirectional"))
    )
    (net (code "120") (name "unconnected-(U3-USB_DP-PadP$26)") (class "Default")
      (node (ref "U3") (pin "P$26") (pinfunction "USB_DP_P$26") (pintype "bidirectional"))
    )
    (net (code "121") (name "unconnected-(X7-5-PadC6)") (class "Default")
      (node (ref "X7") (pin "C6") (pinfunction "5_C6") (pintype "passive"))
    )
  )
)
